# USBCONN_3_A.net
KiCad netlist of a schematic drawn in Altium Designer
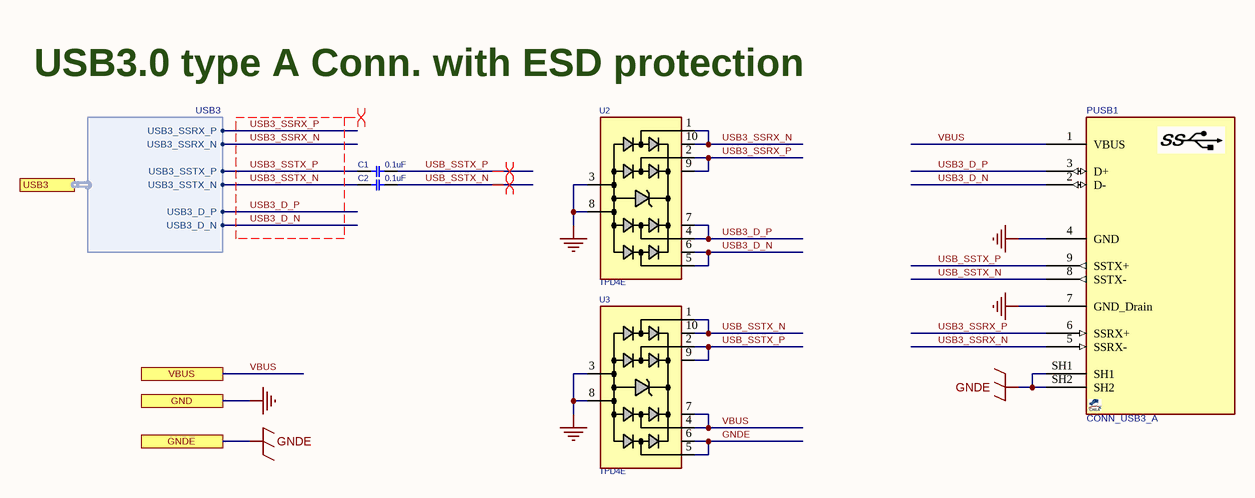
[diagram p0: USBCONN_3_A.SchDoc]

(export (version "E")
  (design (tool "Eeschema 10.0.6"))
  (components
    (comp (ref "C1")
      (value "0.1uF")
      (footprint "C0201")
      (description "CAP, MLCC")
      (fields (field (name "MANF_P#") "GRM155R61E104") (field (name "MANF") "Murata"))
      (libsource (lib "passive_smd") (part "CAP_SMD_MLCC"))
    )
    (comp (ref "C2")
      (value "0.1uF")
      (footprint "C0201")
      (description "CAP, MLCC")
      (fields (field (name "MANF_P#") "GRM155R61E104") (field (name "MANF") "Murata"))
      (libsource (lib "passive_smd") (part "CAP_SMD_MLCC"))
    )
    (comp (ref "PUSB1")
      (value "CONN_USB3_A")
      (footprint "USB3_A_RA")
      (description "CONN, USB3, A type, R/A, THD")
      (fields (field (name "MANF_P#") "USB1075") (field (name "MANF") "GCT"))
      (libsource (lib "conn_usb") (part "CONN_USB3_A_USB1075"))
    )
    (comp (ref "U2")
      (value "TPD4E")
      (footprint "SON50_10_2510")
      (description "TVS, ESD PROTECT, 4CH,")
      (fields (field (name "MANF_P#") "TPD4E05U06DQA") (field (name "MANF") "Texas Instruments"))
      (libsource (lib "protect_tvs_esd_fuse") (part "TVS_X4_TPD4E05U06"))
    )
    (comp (ref "U3")
      (value "TPD4E")
      (footprint "SON50_10_2510")
      (description "TVS, ESD PROTECT, 4CH,")
      (fields (field (name "MANF_P#") "TPD4E05U06DQA") (field (name "MANF") "Texas Instruments"))
      (libsource (lib "protect_tvs_esd_fuse") (part "TVS_X4_TPD4E05U06"))
    )
  )
  (nets
    (net (code "2") (name "/USB3_D_N") (class "Default")
      (node (ref "PUSB1") (pin "2") (pinfunction "D-_2") (pintype "bidirectional"))
      (node (ref "U2") (pin "5") (pinfunction "5_5") (pintype "passive"))
      (node (ref "U2") (pin "6") (pinfunction "6_6") (pintype "passive"))
    )
    (net (code "3") (name "/USB3_D_P") (class "Default")
      (node (ref "PUSB1") (pin "3") (pinfunction "D+_3") (pintype "bidirectional"))
      (node (ref "U2") (pin "4") (pinfunction "4_4") (pintype "passive"))
      (node (ref "U2") (pin "7") (pinfunction "7_7") (pintype "passive"))
    )
    (net (code "4") (name "/USB3_SSRX_N") (class "Default")
      (node (ref "PUSB1") (pin "5") (pinfunction "SSRX-_5") (pintype "input"))
      (node (ref "U2") (pin "1") (pinfunction "1_1") (pintype "passive"))
      (node (ref "U2") (pin "10") (pinfunction "10_10") (pintype "passive"))
    )
    (net (code "5") (name "/USB3_SSRX_P") (class "Default")
      (node (ref "PUSB1") (pin "6") (pinfunction "SSRX+_6") (pintype "input"))
      (node (ref "U2") (pin "2") (pinfunction "2_2") (pintype "passive"))
      (node (ref "U2") (pin "9") (pinfunction "9_9") (pintype "passive"))
    )
    (net (code "6") (name "/USB3_SSTX_N") (class "Default")
      (node (ref "C2") (pin "1") (pinfunction "1_1") (pintype "passive"))
    )
    (net (code "7") (name "/USB3_SSTX_P") (class "Default")
      (node (ref "C1") (pin "1") (pinfunction "1_1") (pintype "passive"))
    )
    (net (code "8") (name "/USB_SSTX_N") (class "Default")
      (node (ref "C2") (pin "2") (pinfunction "2_2") (pintype "passive"))
      (node (ref "PUSB1") (pin "8") (pinfunction "SSTX-_8") (pintype "output"))
      (node (ref "U3") (pin "1") (pinfunction "1_1") (pintype "passive"))
      (node (ref "U3") (pin "10") (pinfunction "10_10") (pintype "passive"))
    )
    (net (code "9") (name "/USB_SSTX_P") (class "Default")
      (node (ref "C1") (pin "2") (pinfunction "2_2") (pintype "passive"))
      (node (ref "PUSB1") (pin "9") (pinfunction "SSTX+_9") (pintype "output"))
      (node (ref "U3") (pin "2") (pinfunction "2_2") (pintype "passive"))
      (node (ref "U3") (pin "9") (pinfunction "9_9") (pintype "passive"))
    )
    (net (code "10") (name "/VBUS") (class "Default")
      (node (ref "PUSB1") (pin "1") (pinfunction "VBUS_1") (pintype "power_in"))
      (node (ref "U3") (pin "4") (pinfunction "4_4") (pintype "passive"))
      (node (ref "U3") (pin "7") (pinfunction "7_7") (pintype "passive"))
    )
    (net (code "12") (name "GND") (class "Default")
      (node (ref "PUSB1") (pin "4") (pinfunction "GND_4") (pintype "power_in"))
      (node (ref "PUSB1") (pin "7") (pinfunction "GND_Drain_7") (pintype "power_in"))
      (node (ref "U2") (pin "3") (pinfunction "3_3") (pintype "passive"))
      (node (ref "U2") (pin "8") (pinfunction "8_8") (pintype "passive"))
      (node (ref "U3") (pin "3") (pinfunction "3_3") (pintype "passive"))
      (node (ref "U3") (pin "8") (pinfunction "8_8") (pintype "passive"))
    )
    (net (code "13") (name "GNDE") (class "Default")
      (node (ref "PUSB1") (pin "SH1") (pinfunction "SH1_SH1") (pintype "passive"))
      (node (ref "PUSB1") (pin "SH2") (pinfunction "SH2_SH2") (pintype "passive"))
      (node (ref "U3") (pin "5") (pinfunction "5_5") (pintype "passive"))
      (node (ref "U3") (pin "6") (pinfunction "6_6") (pintype "passive"))
    )
  )
)
